# SATELLITE.net
KiCad netlist of a schematic drawn in EAGLE
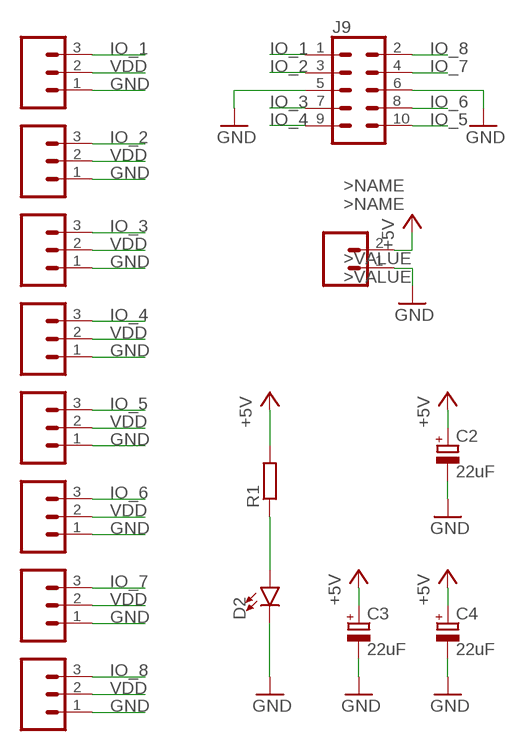
[diagram p0: schematic, sheet 1]

(export (version "E")
  (design (tool "Eeschema 10.0.6"))
  (components
    (comp (ref "C2")
      (value "22uF")
      (footprint "eagle-import:E2-5")
      (libsource (lib "eagle-import") (part "CPOL-EUE2-5"))
    )
    (comp (ref "C3")
      (value "22uF")
      (footprint "eagle-import:E2-5")
      (libsource (lib "eagle-import") (part "CPOL-EUE2-5"))
    )
    (comp (ref "C4")
      (value "22uF")
      (footprint "eagle-import:E2-5")
      (libsource (lib "eagle-import") (part "CPOL-EUE2-5"))
    )
    (comp (ref "D2")
      (value "LED3MM")
      (footprint "eagle-import:LED_3MM")
      (libsource (lib "eagle-import") (part "LED3MM"))
    )
    (comp (ref "J1")
      (value "CONN_03POLAR")
      (footprint "eagle-import:MOLEX-1X3")
      (libsource (lib "eagle-import") (part "CONN_03POLAR"))
    )
    (comp (ref "J2")
      (value "CONN_03POLAR")
      (footprint "eagle-import:MOLEX-1X3")
      (libsource (lib "eagle-import") (part "CONN_03POLAR"))
    )
    (comp (ref "J3")
      (value "CONN_03POLAR")
      (footprint "eagle-import:MOLEX-1X3")
      (libsource (lib "eagle-import") (part "CONN_03POLAR"))
    )
    (comp (ref "J4")
      (value "CONN_03POLAR")
      (footprint "eagle-import:MOLEX-1X3")
      (libsource (lib "eagle-import") (part "CONN_03POLAR"))
    )
    (comp (ref "J5")
      (value "CONN_03POLAR")
      (footprint "eagle-import:MOLEX-1X3")
      (libsource (lib "eagle-import") (part "CONN_03POLAR"))
    )
    (comp (ref "J6")
      (value "CONN_03POLAR")
      (footprint "eagle-import:MOLEX-1X3")
      (libsource (lib "eagle-import") (part "CONN_03POLAR"))
    )
    (comp (ref "J7")
      (value "CONN_03POLAR")
      (footprint "eagle-import:MOLEX-1X3")
      (libsource (lib "eagle-import") (part "CONN_03POLAR"))
    )
    (comp (ref "J8")
      (value "CONN_03POLAR")
      (footprint "eagle-import:MOLEX-1X3")
      (libsource (lib "eagle-import") (part "CONN_03POLAR"))
    )
    (comp (ref "J9")
      (value "CONN_05X2SHD")
      (footprint "eagle-import:2X5-SHROUDED")
      (libsource (lib "eagle-import") (part "CONN_05X2SHD"))
    )
    (comp (ref "J10")
      (value "CONN_02POLAR")
      (footprint "eagle-import:MOLEX-1X2")
      (libsource (lib "eagle-import") (part "CONN_02POLAR"))
    )
    (comp (ref "R1")
      (value "R-EU_0204/7")
      (footprint "eagle-import:0204_7")
      (libsource (lib "eagle-import") (part "R-EU_0204/7"))
    )
  )
  (nets
    (net (code "1") (name "+5V") (class "Default")
      (node (ref "C2") (pin "+") (pinfunction "+_+") (pintype "passive"))
      (node (ref "C3") (pin "+") (pinfunction "+_+") (pintype "passive"))
      (node (ref "C4") (pin "+") (pinfunction "+_+") (pintype "passive"))
      (node (ref "J1") (pin "2") (pinfunction "2_2") (pintype "passive"))
      (node (ref "J10") (pin "2") (pinfunction "2_2") (pintype "passive"))
      (node (ref "J2") (pin "2") (pinfunction "2_2") (pintype "passive"))
      (node (ref "J3") (pin "2") (pinfunction "2_2") (pintype "passive"))
      (node (ref "J4") (pin "2") (pinfunction "2_2") (pintype "passive"))
      (node (ref "J5") (pin "2") (pinfunction "2_2") (pintype "passive"))
      (node (ref "J6") (pin "2") (pinfunction "2_2") (pintype "passive"))
      (node (ref "J7") (pin "2") (pinfunction "2_2") (pintype "passive"))
      (node (ref "J8") (pin "2") (pinfunction "2_2") (pintype "passive"))
      (node (ref "R1") (pin "2") (pinfunction "2_2") (pintype "passive"))
    )
    (net (code "2") (name "/IO_1") (class "Default")
      (node (ref "J7") (pin "3") (pinfunction "3_3") (pintype "passive"))
      (node (ref "J9") (pin "1") (pinfunction "1_1") (pintype "passive"))
    )
    (net (code "3") (name "/IO_2") (class "Default")
      (node (ref "J8") (pin "3") (pinfunction "3_3") (pintype "passive"))
      (node (ref "J9") (pin "3") (pinfunction "3_3") (pintype "passive"))
    )
    (net (code "4") (name "/IO_3") (class "Default")
      (node (ref "J1") (pin "3") (pinfunction "3_3") (pintype "passive"))
      (node (ref "J9") (pin "7") (pinfunction "7_7") (pintype "passive"))
    )
    (net (code "5") (name "/IO_4") (class "Default")
      (node (ref "J2") (pin "3") (pinfunction "3_3") (pintype "passive"))
      (node (ref "J9") (pin "9") (pinfunction "9_9") (pintype "passive"))
    )
    (net (code "6") (name "/IO_5") (class "Default")
      (node (ref "J3") (pin "3") (pinfunction "3_3") (pintype "passive"))
      (node (ref "J9") (pin "10") (pinfunction "10_10") (pintype "passive"))
    )
    (net (code "7") (name "/IO_6") (class "Default")
      (node (ref "J4") (pin "3") (pinfunction "3_3") (pintype "passive"))
      (node (ref "J9") (pin "8") (pinfunction "8_8") (pintype "passive"))
    )
    (net (code "8") (name "/IO_7") (class "Default")
      (node (ref "J5") (pin "3") (pinfunction "3_3") (pintype "passive"))
      (node (ref "J9") (pin "4") (pinfunction "4_4") (pintype "passive"))
    )
    (net (code "9") (name "/IO_8") (class "Default")
      (node (ref "J6") (pin "3") (pinfunction "3_3") (pintype "passive"))
      (node (ref "J9") (pin "2") (pinfunction "2_2") (pintype "passive"))
    )
    (net (code "10") (name "GND") (class "Default")
      (node (ref "C2") (pin "-") (pinfunction "-_-") (pintype "passive"))
      (node (ref "C3") (pin "-") (pinfunction "-_-") (pintype "passive"))
      (node (ref "C4") (pin "-") (pinfunction "-_-") (pintype "passive"))
      (node (ref "D2") (pin "K") (pinfunction "C_K") (pintype "passive"))
      (node (ref "J1") (pin "1") (pinfunction "1_1") (pintype "passive"))
      (node (ref "J10") (pin "1") (pinfunction "1_1") (pintype "passive"))
      (node (ref "J2") (pin "1") (pinfunction "1_1") (pintype "passive"))
      (node (ref "J3") (pin "1") (pinfunction "1_1") (pintype "passive"))
      (node (ref "J4") (pin "1") (pinfunction "1_1") (pintype "passive"))
      (node (ref "J5") (pin "1") (pinfunction "1_1") (pintype "passive"))
      (node (ref "J6") (pin "1") (pinfunction "1_1") (pintype "passive"))
      (node (ref "J7") (pin "1") (pinfunction "1_1") (pintype "passive"))
      (node (ref "J8") (pin "1") (pinfunction "1_1") (pintype "passive"))
      (node (ref "J9") (pin "5") (pinfunction "5_5") (pintype "passive"))
      (node (ref "J9") (pin "6") (pinfunction "6_6") (pintype "passive"))
    )
    (net (code "11") (name "Net-(D2-PadA)") (class "Default")
      (node (ref "D2") (pin "A") (pinfunction "A_A") (pintype "passive"))
      (node (ref "R1") (pin "1") (pinfunction "1_1") (pintype "passive"))
    )
  )
)
